# FluxCapacitorCPUMeter.net
KiCad netlist of a schematic drawn in EAGLE
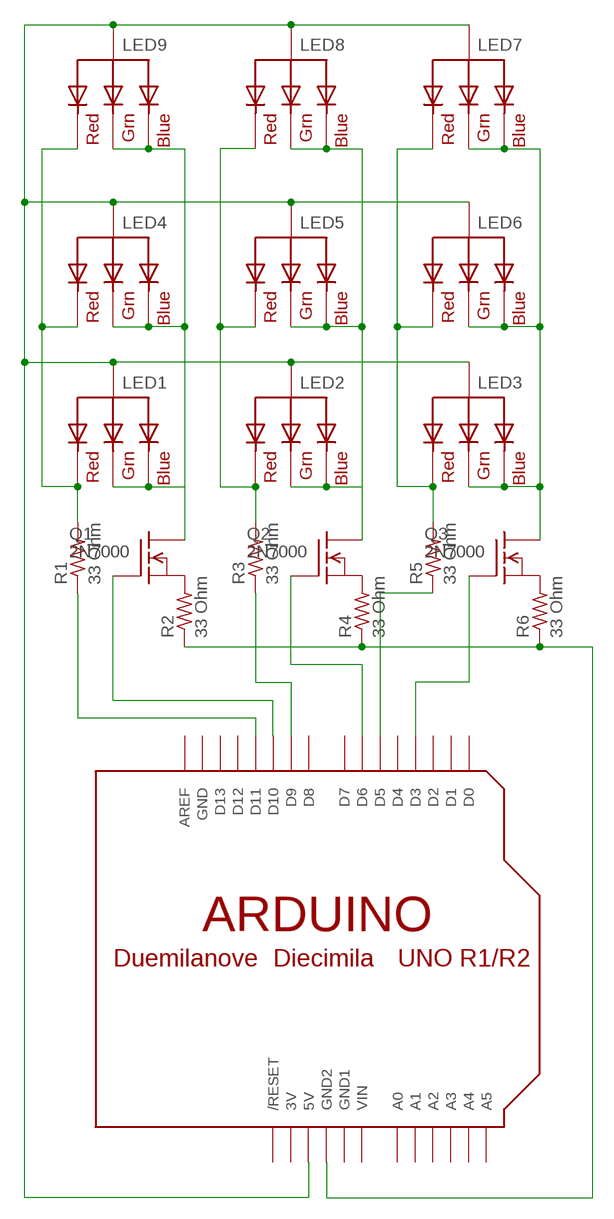
[diagram p0: schematic, sheet 1]

(export (version "E")
  (design (tool "Eeschema 10.0.6"))
  (components
    (comp (ref "LED1")
      (value "RGBLED_CA-5MM")
      (footprint "eagle-import:LED5MMRGB")
      (libsource (lib "eagle-import") (part "RGBLED_CA-5MM"))
    )
    (comp (ref "LED2")
      (value "RGBLED_CA-5MM")
      (footprint "eagle-import:LED5MMRGB")
      (libsource (lib "eagle-import") (part "RGBLED_CA-5MM"))
    )
    (comp (ref "LED3")
      (value "RGBLED_CA-5MM")
      (footprint "eagle-import:LED5MMRGB")
      (libsource (lib "eagle-import") (part "RGBLED_CA-5MM"))
    )
    (comp (ref "LED4")
      (value "RGBLED_CA-5MM")
      (footprint "eagle-import:LED5MMRGB")
      (libsource (lib "eagle-import") (part "RGBLED_CA-5MM"))
    )
    (comp (ref "LED5")
      (value "RGBLED_CA-5MM")
      (footprint "eagle-import:LED5MMRGB")
      (libsource (lib "eagle-import") (part "RGBLED_CA-5MM"))
    )
    (comp (ref "LED6")
      (value "RGBLED_CA-5MM")
      (footprint "eagle-import:LED5MMRGB")
      (libsource (lib "eagle-import") (part "RGBLED_CA-5MM"))
    )
    (comp (ref "LED7")
      (value "RGBLED_CA-5MM")
      (footprint "eagle-import:LED5MMRGB")
      (libsource (lib "eagle-import") (part "RGBLED_CA-5MM"))
    )
    (comp (ref "LED8")
      (value "RGBLED_CA-5MM")
      (footprint "eagle-import:LED5MMRGB")
      (libsource (lib "eagle-import") (part "RGBLED_CA-5MM"))
    )
    (comp (ref "LED9")
      (value "RGBLED_CA-5MM")
      (footprint "eagle-import:LED5MMRGB")
      (libsource (lib "eagle-import") (part "RGBLED_CA-5MM"))
    )
    (comp (ref "Q1")
      (value "2N7000")
      (footprint "eagle-import:TO92-INLINE")
      (libsource (lib "eagle-import") (part "FQN1N50CI"))
    )
    (comp (ref "Q2")
      (value "2N7000")
      (footprint "eagle-import:TO92-INLINE")
      (libsource (lib "eagle-import") (part "FQN1N50CI"))
    )
    (comp (ref "Q3")
      (value "2N7000")
      (footprint "eagle-import:TO92-INLINE")
      (libsource (lib "eagle-import") (part "FQN1N50CI"))
    )
    (comp (ref "R1")
      (value "33 Ohm")
      (footprint "eagle-import:0207_10")
      (libsource (lib "eagle-import") (part "R-US_0207/10"))
    )
    (comp (ref "R2")
      (value "33 Ohm")
      (footprint "eagle-import:0207_10")
      (libsource (lib "eagle-import") (part "R-US_0207/10"))
    )
    (comp (ref "R3")
      (value "33 Ohm")
      (footprint "eagle-import:0207_10")
      (libsource (lib "eagle-import") (part "R-US_0207/10"))
    )
    (comp (ref "R4")
      (value "33 Ohm")
      (footprint "eagle-import:0207_10")
      (libsource (lib "eagle-import") (part "R-US_0207/10"))
    )
    (comp (ref "R5")
      (value "33 Ohm")
      (footprint "eagle-import:0207_10")
      (libsource (lib "eagle-import") (part "R-US_0207/10"))
    )
    (comp (ref "R6")
      (value "33 Ohm")
      (footprint "eagle-import:0207_10")
      (libsource (lib "eagle-import") (part "R-US_0207/10"))
    )
    (comp (ref "U$1")
      (value "ARDUINOUNO")
      (footprint "eagle-import:ARDUINO")
      (libsource (lib "eagle-import") (part "ARDUINOUNO"))
    )
  )
  (nets
    (net (code "1") (name "/3V") (class "Default")
      (node (ref "U$1") (pin "3V") (pinfunction "3V_3V") (pintype "power_in"))
    )
    (net (code "2") (name "/GND") (class "Default")
      (node (ref "U$1") (pin "GND") (pinfunction "GND_GND") (pintype "power_in"))
    )
    (net (code "3") (name "/GND1") (class "Default")
      (node (ref "U$1") (pin "GND1") (pinfunction "GND1_GND1") (pintype "power_in"))
    )
    (net (code "4") (name "/VIN") (class "Default")
      (node (ref "U$1") (pin "VIN") (pinfunction "VIN_VIN") (pintype "power_in"))
    )
    (net (code "5") (name "Net-(LED1-BLUE)") (class "Default")
      (node (ref "LED1") (pin "3") (pinfunction "GREEN_3") (pintype "bidirectional"))
      (node (ref "LED1") (pin "4") (pinfunction "BLUE_4") (pintype "bidirectional"))
      (node (ref "LED4") (pin "3") (pinfunction "GREEN_3") (pintype "bidirectional"))
      (node (ref "LED4") (pin "4") (pinfunction "BLUE_4") (pintype "bidirectional"))
      (node (ref "LED9") (pin "3") (pinfunction "GREEN_3") (pintype "bidirectional"))
      (node (ref "LED9") (pin "4") (pinfunction "BLUE_4") (pintype "bidirectional"))
      (node (ref "Q1") (pin "1") (pinfunction "D_1") (pintype "passive"))
    )
    (net (code "6") (name "Net-(LED1-RED)") (class "Default")
      (node (ref "LED1") (pin "1") (pinfunction "RED_1") (pintype "bidirectional"))
      (node (ref "LED4") (pin "1") (pinfunction "RED_1") (pintype "bidirectional"))
      (node (ref "LED9") (pin "1") (pinfunction "RED_1") (pintype "bidirectional"))
      (node (ref "R1") (pin "2") (pinfunction "2_2") (pintype "passive"))
    )
    (net (code "7") (name "Net-(LED1-VCC)") (class "Default")
      (node (ref "LED1") (pin "2") (pinfunction "VCC_2") (pintype "bidirectional"))
      (node (ref "LED2") (pin "2") (pinfunction "VCC_2") (pintype "bidirectional"))
      (node (ref "LED3") (pin "2") (pinfunction "VCC_2") (pintype "bidirectional"))
      (node (ref "LED4") (pin "2") (pinfunction "VCC_2") (pintype "bidirectional"))
      (node (ref "LED5") (pin "2") (pinfunction "VCC_2") (pintype "bidirectional"))
      (node (ref "LED6") (pin "2") (pinfunction "VCC_2") (pintype "bidirectional"))
      (node (ref "LED7") (pin "2") (pinfunction "VCC_2") (pintype "bidirectional"))
      (node (ref "LED8") (pin "2") (pinfunction "VCC_2") (pintype "bidirectional"))
      (node (ref "LED9") (pin "2") (pinfunction "VCC_2") (pintype "bidirectional"))
      (node (ref "U$1") (pin "5V") (pinfunction "5V_5V") (pintype "power_in"))
    )
    (net (code "8") (name "Net-(LED2-BLUE)") (class "Default")
      (node (ref "LED2") (pin "3") (pinfunction "GREEN_3") (pintype "bidirectional"))
      (node (ref "LED2") (pin "4") (pinfunction "BLUE_4") (pintype "bidirectional"))
      (node (ref "LED5") (pin "3") (pinfunction "GREEN_3") (pintype "bidirectional"))
      (node (ref "LED5") (pin "4") (pinfunction "BLUE_4") (pintype "bidirectional"))
      (node (ref "LED8") (pin "3") (pinfunction "GREEN_3") (pintype "bidirectional"))
      (node (ref "LED8") (pin "4") (pinfunction "BLUE_4") (pintype "bidirectional"))
      (node (ref "Q2") (pin "1") (pinfunction "D_1") (pintype "passive"))
    )
    (net (code "9") (name "Net-(LED2-RED)") (class "Default")
      (node (ref "LED2") (pin "1") (pinfunction "RED_1") (pintype "bidirectional"))
      (node (ref "LED5") (pin "1") (pinfunction "RED_1") (pintype "bidirectional"))
      (node (ref "LED8") (pin "1") (pinfunction "RED_1") (pintype "bidirectional"))
      (node (ref "R3") (pin "2") (pinfunction "2_2") (pintype "passive"))
    )
    (net (code "10") (name "Net-(LED3-BLUE)") (class "Default")
      (node (ref "LED3") (pin "3") (pinfunction "GREEN_3") (pintype "bidirectional"))
      (node (ref "LED3") (pin "4") (pinfunction "BLUE_4") (pintype "bidirectional"))
      (node (ref "LED6") (pin "3") (pinfunction "GREEN_3") (pintype "bidirectional"))
      (node (ref "LED6") (pin "4") (pinfunction "BLUE_4") (pintype "bidirectional"))
      (node (ref "LED7") (pin "3") (pinfunction "GREEN_3") (pintype "bidirectional"))
      (node (ref "LED7") (pin "4") (pinfunction "BLUE_4") (pintype "bidirectional"))
      (node (ref "Q3") (pin "1") (pinfunction "D_1") (pintype "passive"))
    )
    (net (code "11") (name "Net-(LED3-RED)") (class "Default")
      (node (ref "LED3") (pin "1") (pinfunction "RED_1") (pintype "bidirectional"))
      (node (ref "LED6") (pin "1") (pinfunction "RED_1") (pintype "bidirectional"))
      (node (ref "LED7") (pin "1") (pinfunction "RED_1") (pintype "bidirectional"))
      (node (ref "R5") (pin "2") (pinfunction "2_2") (pintype "passive"))
    )
    (net (code "12") (name "Net-(Q1-G)") (class "Default")
      (node (ref "Q1") (pin "2") (pinfunction "G_2") (pintype "passive"))
      (node (ref "U$1") (pin "D10") (pinfunction "D10_D10") (pintype "bidirectional"))
    )
    (net (code "13") (name "Net-(Q1-S)") (class "Default")
      (node (ref "Q1") (pin "3") (pinfunction "S_3") (pintype "passive"))
      (node (ref "R2") (pin "2") (pinfunction "2_2") (pintype "passive"))
    )
    (net (code "14") (name "Net-(Q2-G)") (class "Default")
      (node (ref "Q2") (pin "2") (pinfunction "G_2") (pintype "passive"))
      (node (ref "U$1") (pin "D6") (pinfunction "D6_D6") (pintype "bidirectional"))
    )
    (net (code "15") (name "Net-(Q2-S)") (class "Default")
      (node (ref "Q2") (pin "3") (pinfunction "S_3") (pintype "passive"))
      (node (ref "R4") (pin "2") (pinfunction "2_2") (pintype "passive"))
    )
    (net (code "16") (name "Net-(Q3-G)") (class "Default")
      (node (ref "Q3") (pin "2") (pinfunction "G_2") (pintype "passive"))
      (node (ref "U$1") (pin "D3") (pinfunction "D3_D3") (pintype "bidirectional"))
    )
    (net (code "17") (name "Net-(Q3-S)") (class "Default")
      (node (ref "Q3") (pin "3") (pinfunction "S_3") (pintype "passive"))
      (node (ref "R6") (pin "2") (pinfunction "2_2") (pintype "passive"))
    )
    (net (code "18") (name "Net-(R1-Pad1)") (class "Default")
      (node (ref "R1") (pin "1") (pinfunction "1_1") (pintype "passive"))
      (node (ref "U$1") (pin "D11") (pinfunction "D11_D11") (pintype "bidirectional"))
    )
    (net (code "19") (name "Net-(R2-Pad1)") (class "Default")
      (node (ref "R2") (pin "1") (pinfunction "1_1") (pintype "passive"))
      (node (ref "R4") (pin "1") (pinfunction "1_1") (pintype "passive"))
      (node (ref "R6") (pin "1") (pinfunction "1_1") (pintype "passive"))
      (node (ref "U$1") (pin "GND2") (pinfunction "GND2_GND2") (pintype "power_in"))
    )
    (net (code "20") (name "Net-(R3-Pad1)") (class "Default")
      (node (ref "R3") (pin "1") (pinfunction "1_1") (pintype "passive"))
      (node (ref "U$1") (pin "D9") (pinfunction "D9_D9") (pintype "bidirectional"))
    )
    (net (code "21") (name "Net-(R5-Pad1)") (class "Default")
      (node (ref "R5") (pin "1") (pinfunction "1_1") (pintype "passive"))
      (node (ref "U$1") (pin "D5") (pinfunction "D5_D5") (pintype "bidirectional"))
    )
    (net (code "22") (name "unconnected-(U$1-PadA0)") (class "Default")
      (node (ref "U$1") (pin "A0") (pinfunction "A0_A0") (pintype "bidirectional"))
    )
    (net (code "23") (name "unconnected-(U$1-PadA1)") (class "Default")
      (node (ref "U$1") (pin "A1") (pinfunction "A1_A1") (pintype "bidirectional"))
    )
    (net (code "24") (name "unconnected-(U$1-PadA2)") (class "Default")
      (node (ref "U$1") (pin "A2") (pinfunction "A2_A2") (pintype "bidirectional"))
    )
    (net (code "25") (name "unconnected-(U$1-PadA3)") (class "Default")
      (node (ref "U$1") (pin "A3") (pinfunction "A3_A3") (pintype "bidirectional"))
    )
    (net (code "26") (name "unconnected-(U$1-PadA4)") (class "Default")
      (node (ref "U$1") (pin "A4") (pinfunction "A4_A4") (pintype "bidirectional"))
    )
    (net (code "27") (name "unconnected-(U$1-PadA5)") (class "Default")
      (node (ref "U$1") (pin "A5") (pinfunction "A5_A5") (pintype "bidirectional"))
    )
    (net (code "28") (name "unconnected-(U$1-PadAREF)") (class "Default")
      (node (ref "U$1") (pin "AREF") (pinfunction "AREF_AREF") (pintype "bidirectional"))
    )
    (net (code "29") (name "unconnected-(U$1-PadD0)") (class "Default")
      (node (ref "U$1") (pin "D0") (pinfunction "D0_D0") (pintype "bidirectional"))
    )
    (net (code "30") (name "unconnected-(U$1-PadD1)") (class "Default")
      (node (ref "U$1") (pin "D1") (pinfunction "D1_D1") (pintype "bidirectional"))
    )
    (net (code "31") (name "unconnected-(U$1-PadD2)") (class "Default")
      (node (ref "U$1") (pin "D2") (pinfunction "D2_D2") (pintype "bidirectional"))
    )
    (net (code "32") (name "unconnected-(U$1-PadD4)") (class "Default")
      (node (ref "U$1") (pin "D4") (pinfunction "D4_D4") (pintype "bidirectional"))
    )
    (net (code "33") (name "unconnected-(U$1-PadD7)") (class "Default")
      (node (ref "U$1") (pin "D7") (pinfunction "D7_D7") (pintype "bidirectional"))
    )
    (net (code "34") (name "unconnected-(U$1-PadD8)") (class "Default")
      (node (ref "U$1") (pin "D8") (pinfunction "D8_D8") (pintype "bidirectional"))
    )
    (net (code "35") (name "unconnected-(U$1-PadD12)") (class "Default")
      (node (ref "U$1") (pin "D12") (pinfunction "D12_D12") (pintype "bidirectional"))
    )
    (net (code "36") (name "unconnected-(U$1-PadD13)") (class "Default")
      (node (ref "U$1") (pin "D13") (pinfunction "D13_D13") (pintype "bidirectional"))
    )
    (net (code "37") (name "unconnected-(U$1-{slash}RESET-PadRESET)") (class "Default")
      (node (ref "U$1") (pin "RESET") (pinfunction "/RESET_RESET") (pintype "bidirectional"))
    )
  )
)
